# board1.net
KiCad netlist of a schematic drawn in EAGLE
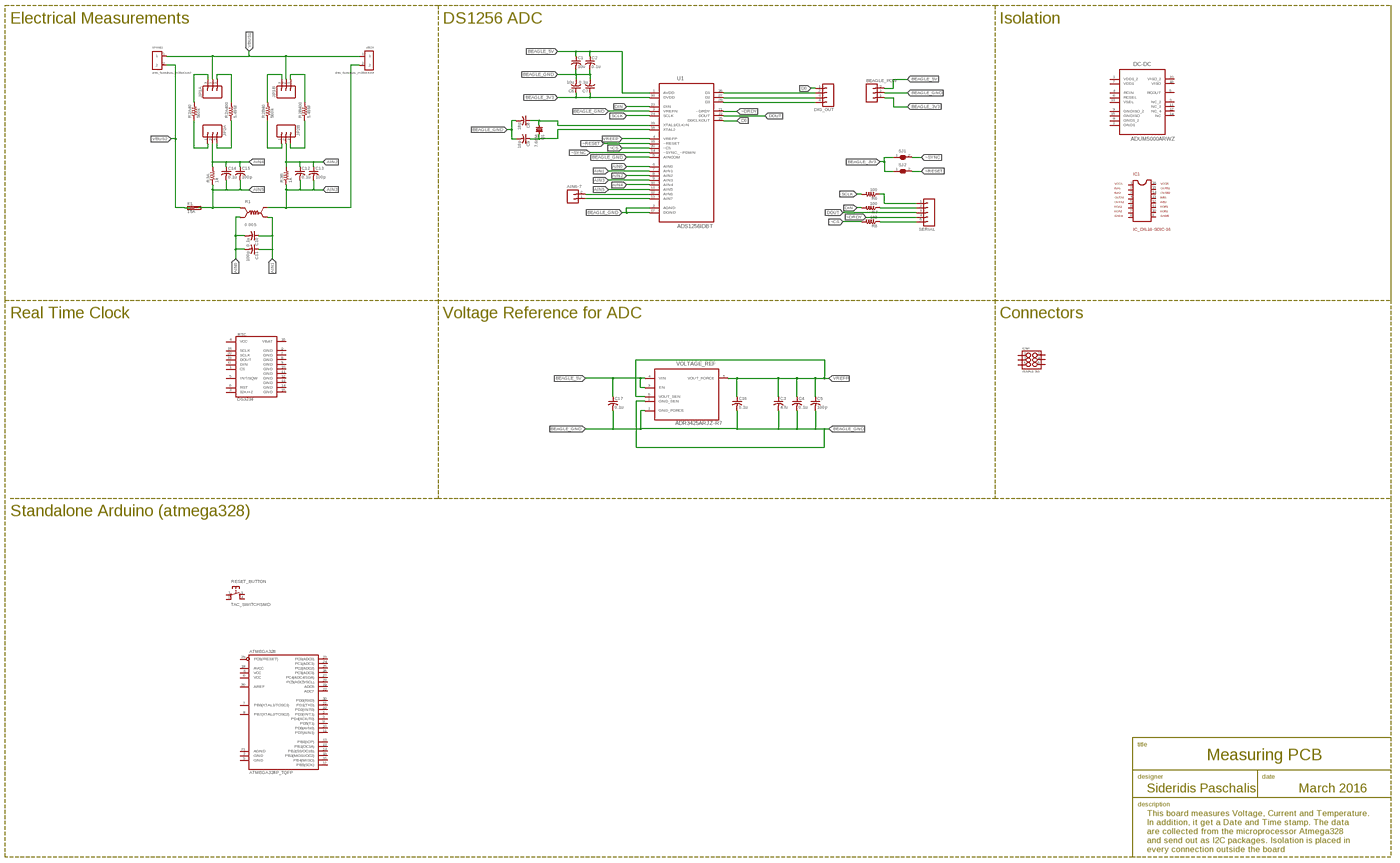
[diagram p0: schematic, sheet 1, overview]
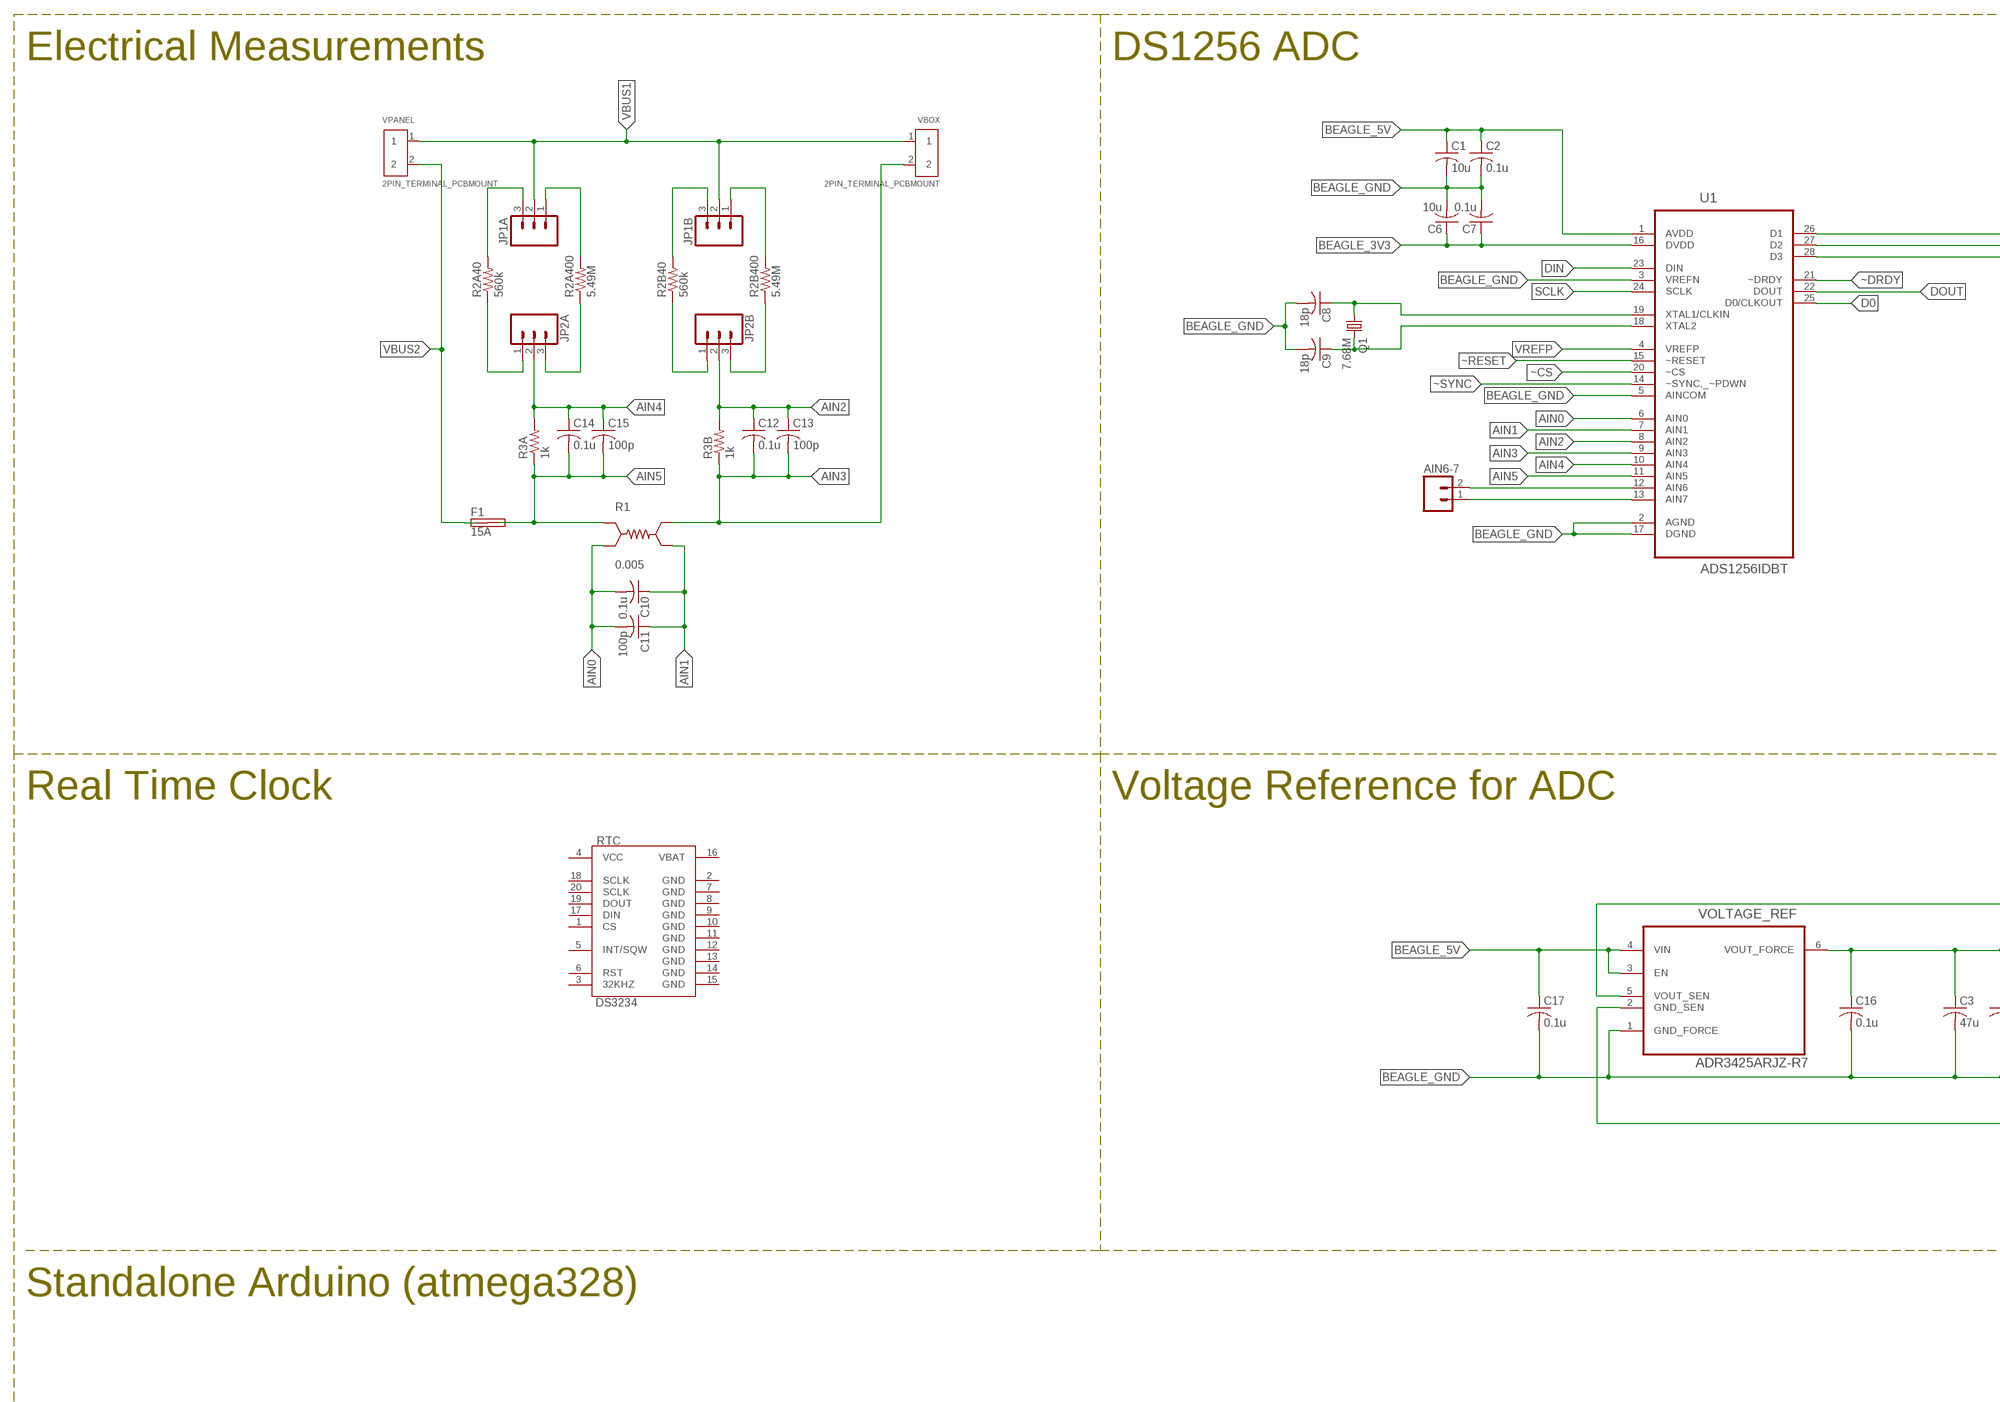
[diagram p1: schematic, sheet 1, part 1 of 4]
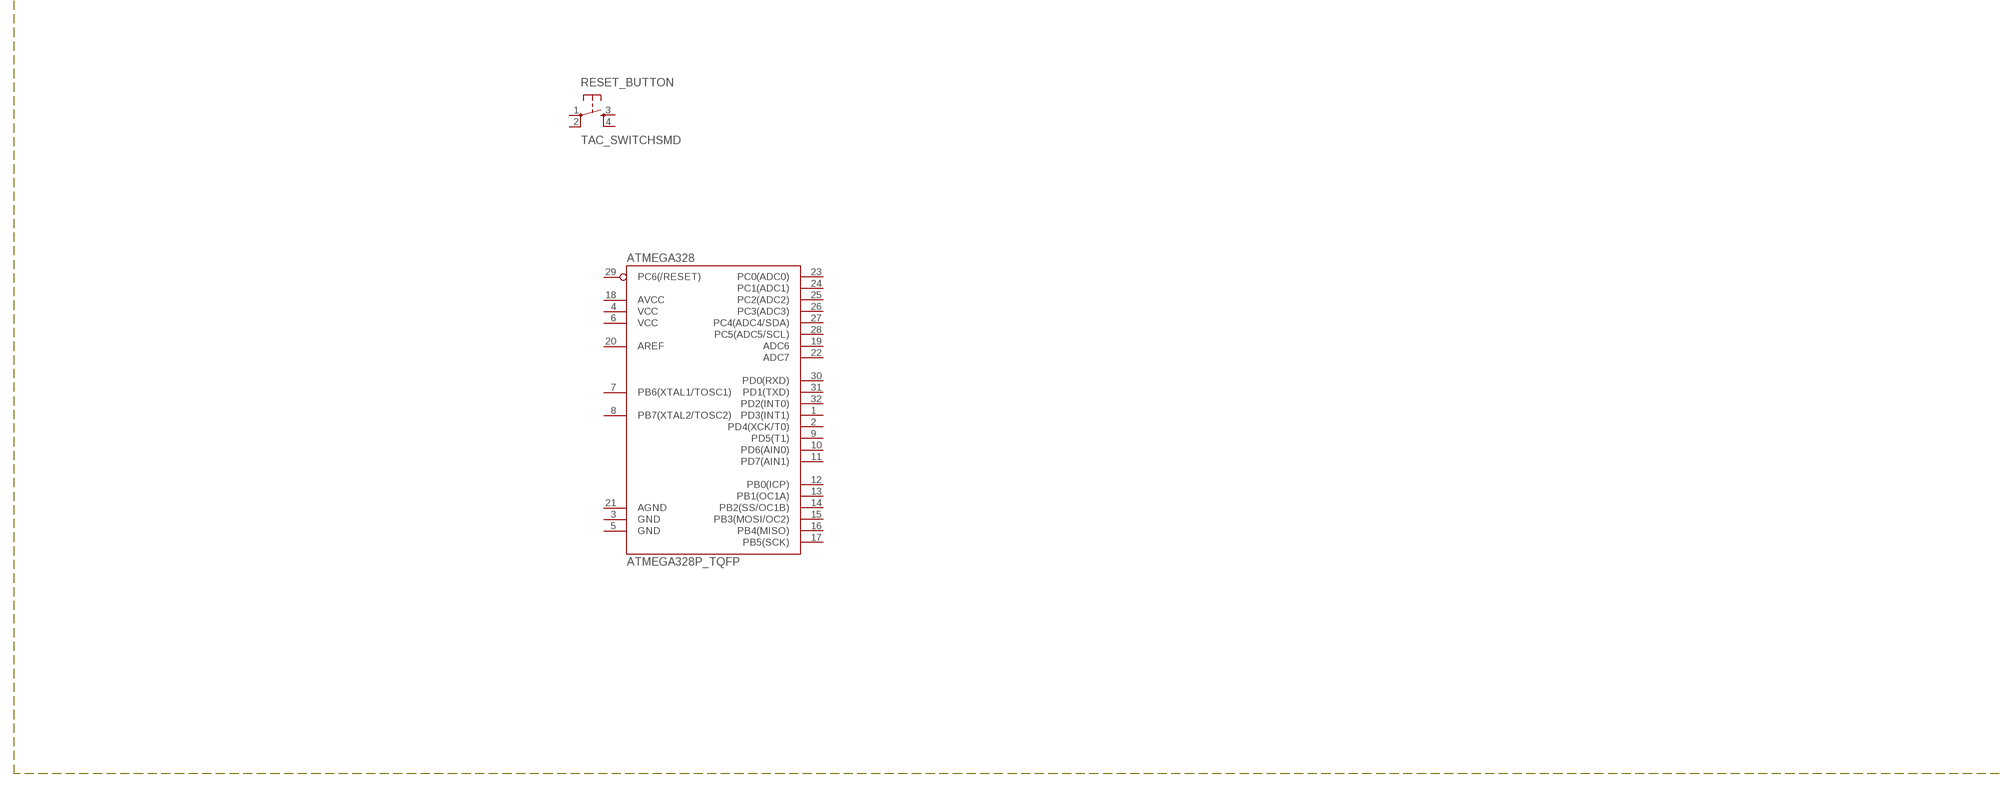
[diagram p2: schematic, sheet 1, part 2 of 4]
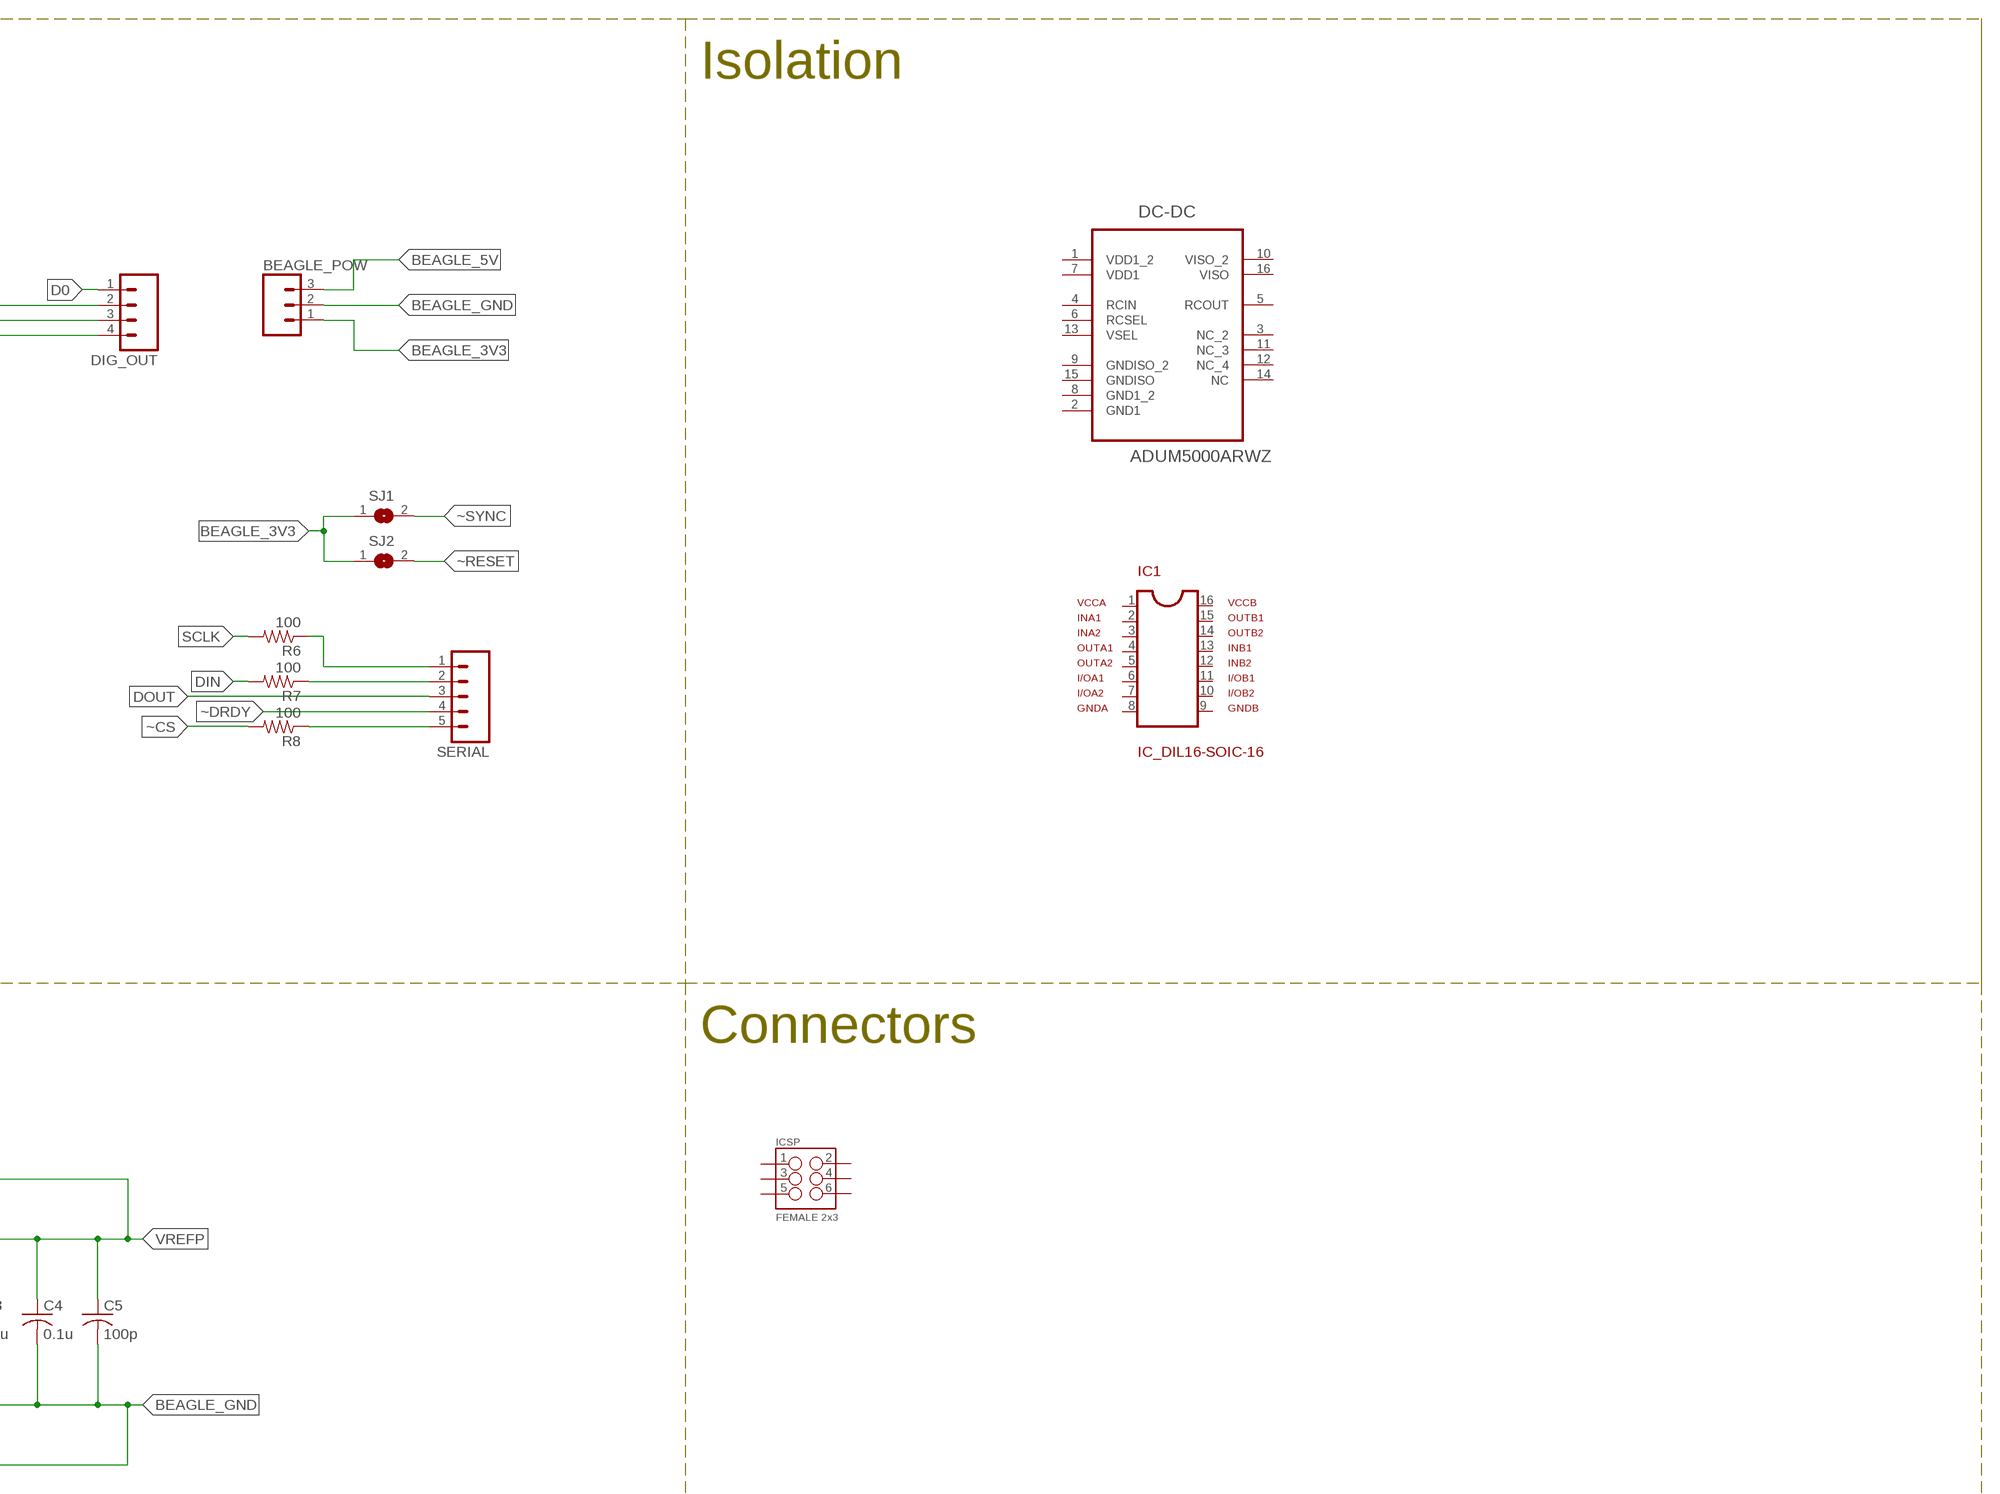
[diagram p3: schematic, sheet 1, part 3 of 4]
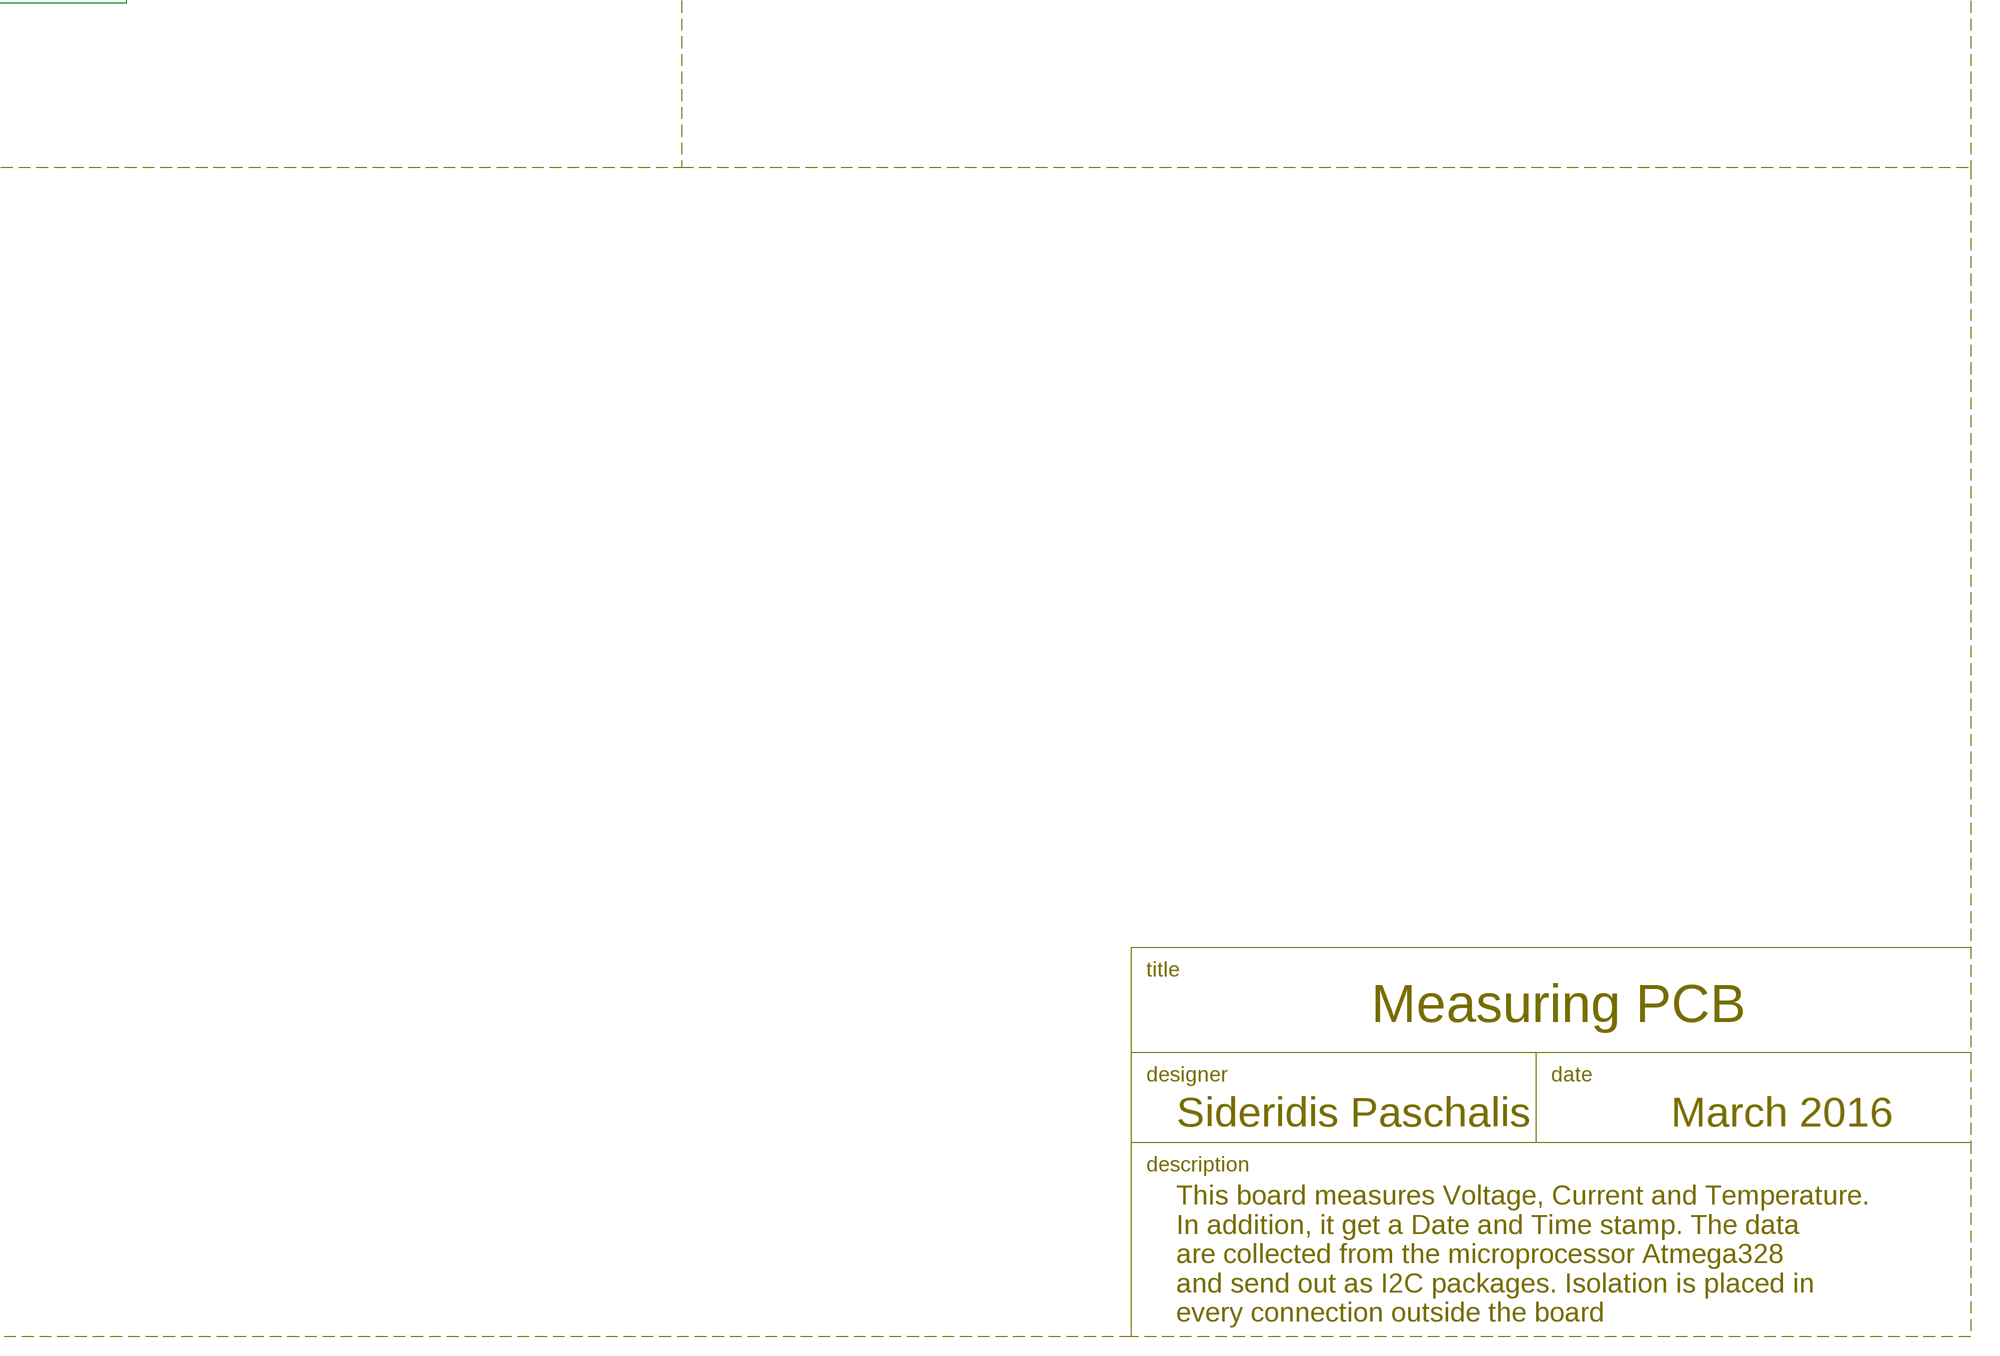
[diagram p4: schematic, sheet 1, part 4 of 4]

(export (version "E")
  (design (tool "Eeschema 10.0.6"))
  (components
    (comp (ref "AIN6-7")
      (value "M02PTH")
      (footprint "eagle-import:1X02")
      (libsource (lib "eagle-import") (part "M02PTH"))
    )
    (comp (ref "ATMEGA328")
      (value "ATMEGA328P_TQFP")
      (footprint "eagle-import:TQFP32-08")
      (libsource (lib "eagle-import") (part "ATMEGA328P_TQFP"))
    )
    (comp (ref "BEAGLE_POW")
      (value "M03PTH")
      (footprint "eagle-import:1X03")
      (libsource (lib "eagle-import") (part "M03PTH"))
    )
    (comp (ref "C1")
      (value "10u")
      (footprint "eagle-import:C3216")
      (libsource (lib "eagle-import") (part "C-USC3216"))
    )
    (comp (ref "C2")
      (value "0.1u")
      (footprint "eagle-import:C3216")
      (libsource (lib "eagle-import") (part "C-USC3216"))
    )
    (comp (ref "C3")
      (value "47u")
      (footprint "eagle-import:C3216")
      (libsource (lib "eagle-import") (part "C-USC3216"))
    )
    (comp (ref "C4")
      (value "0.1u")
      (footprint "eagle-import:C3216")
      (libsource (lib "eagle-import") (part "C-USC3216"))
    )
    (comp (ref "C5")
      (value "100p")
      (footprint "eagle-import:C3216")
      (libsource (lib "eagle-import") (part "C-USC3216"))
    )
    (comp (ref "C6")
      (value "10u")
      (footprint "eagle-import:C3216")
      (libsource (lib "eagle-import") (part "C-USC3216"))
    )
    (comp (ref "C7")
      (value "0.1u")
      (footprint "eagle-import:C3216")
      (libsource (lib "eagle-import") (part "C-USC3216"))
    )
    (comp (ref "C8")
      (value "18p")
      (footprint "eagle-import:C3216")
      (libsource (lib "eagle-import") (part "C-USC3216"))
    )
    (comp (ref "C9")
      (value "18p")
      (footprint "eagle-import:C3216")
      (libsource (lib "eagle-import") (part "C-USC3216"))
    )
    (comp (ref "C10")
      (value "0.1u")
      (footprint "eagle-import:C3216")
      (libsource (lib "eagle-import") (part "C-USC3216"))
    )
    (comp (ref "C11")
      (value "100p")
      (footprint "eagle-import:C3216")
      (libsource (lib "eagle-import") (part "C-USC3216"))
    )
    (comp (ref "C12")
      (value "0.1u")
      (footprint "eagle-import:C3216")
      (libsource (lib "eagle-import") (part "C-USC3216"))
    )
    (comp (ref "C13")
      (value "100p")
      (footprint "eagle-import:C3216")
      (libsource (lib "eagle-import") (part "C-USC3216"))
    )
    (comp (ref "C14")
      (value "0.1u")
      (footprint "eagle-import:C3216")
      (libsource (lib "eagle-import") (part "C-USC3216"))
    )
    (comp (ref "C15")
      (value "100p")
      (footprint "eagle-import:C3216")
      (libsource (lib "eagle-import") (part "C-USC3216"))
    )
    (comp (ref "C16")
      (value "0.1u")
      (footprint "eagle-import:C3216")
      (libsource (lib "eagle-import") (part "C-USC3216"))
    )
    (comp (ref "C17")
      (value "0.1u")
      (footprint "eagle-import:C3216")
      (libsource (lib "eagle-import") (part "C-USC3216"))
    )
    (comp (ref "DC-DC")
      (value "ADUM5000ARWZ")
      (footprint "eagle-import:SOIC127P1032X265-16N")
      (libsource (lib "eagle-import") (part "ADUM5000ARWZ"))
    )
    (comp (ref "DIG_OUT")
      (value "M04PTH")
      (footprint "eagle-import:1X04")
      (libsource (lib "eagle-import") (part "M04PTH"))
    )
    (comp (ref "F1")
      (value "15A")
      (footprint "eagle-import:SHK20L")
      (libsource (lib "eagle-import") (part "SHK20L"))
    )
    (comp (ref "IC1")
      (value "IC_DIL16-SOIC-16")
      (footprint "eagle-import:SOIC-16")
      (libsource (lib "eagle-import") (part "IC_DIL16-SOIC-16"))
    )
    (comp (ref "ICSP")
      (value "FEMALE 2x3")
      (footprint "eagle-import:2X3")
      (libsource (lib "eagle-import") (part "M03X2FEMALE"))
    )
    (comp (ref "JP1A")
      (value "M03PTH")
      (footprint "eagle-import:1X03")
      (libsource (lib "eagle-import") (part "M03PTH"))
    )
    (comp (ref "JP1B")
      (value "M03PTH")
      (footprint "eagle-import:1X03")
      (libsource (lib "eagle-import") (part "M03PTH"))
    )
    (comp (ref "JP2A")
      (value "M03PTH")
      (footprint "eagle-import:1X03")
      (libsource (lib "eagle-import") (part "M03PTH"))
    )
    (comp (ref "JP2B")
      (value "M03PTH")
      (footprint "eagle-import:1X03")
      (libsource (lib "eagle-import") (part "M03PTH"))
    )
    (comp (ref "Q1")
      (value "7.68M")
      (footprint "eagle-import:HC49U-V")
      (libsource (lib "eagle-import") (part "CRYSTALHC49U-V"))
    )
    (comp (ref "R1")
      (value "0.005")
      (footprint "eagle-import:LVK25")
      (libsource (lib "eagle-import") (part "LVK25R001"))
    )
    (comp (ref "R2A40")
      (value "560k")
      (footprint "eagle-import:M3216")
      (libsource (lib "eagle-import") (part "R-US_M3216"))
    )
    (comp (ref "R2A400")
      (value "5.49M")
      (footprint "eagle-import:M3216")
      (libsource (lib "eagle-import") (part "R-US_M3216"))
    )
    (comp (ref "R2B40")
      (value "560k")
      (footprint "eagle-import:M3216")
      (libsource (lib "eagle-import") (part "R-US_M3216"))
    )
    (comp (ref "R2B400")
      (value "5.49M")
      (footprint "eagle-import:M3216")
      (libsource (lib "eagle-import") (part "R-US_M3216"))
    )
    (comp (ref "R3A")
      (value "1k")
      (footprint "eagle-import:M3216")
      (libsource (lib "eagle-import") (part "R-US_M3216"))
    )
    (comp (ref "R3B")
      (value "1k")
      (footprint "eagle-import:M3216")
      (libsource (lib "eagle-import") (part "R-US_M3216"))
    )
    (comp (ref "R6")
      (value "100")
      (footprint "eagle-import:M3216")
      (libsource (lib "eagle-import") (part "R-US_M3216"))
    )
    (comp (ref "R7")
      (value "100")
      (footprint "eagle-import:M3216")
      (libsource (lib "eagle-import") (part "R-US_M3216"))
    )
    (comp (ref "R8")
      (value "100")
      (footprint "eagle-import:M3216")
      (libsource (lib "eagle-import") (part "R-US_M3216"))
    )
    (comp (ref "RESET_BUTTON")
      (value "TAC_SWITCHSMD")
      (footprint "eagle-import:TACTILE-SWITCH-SMD")
      (libsource (lib "eagle-import") (part "TAC_SWITCHSMD"))
    )
    (comp (ref "RTC")
      (value "DS3234")
      (footprint "eagle-import:DS3234")
      (libsource (lib "eagle-import") (part "DS3234"))
    )
    (comp (ref "SERIAL")
      (value "M05PTH")
      (footprint "eagle-import:1X05")
      (libsource (lib "eagle-import") (part "M05PTH"))
    )
    (comp (ref "SJ1") (value "SJ") (footprint "eagle-import:SJ") (libsource (lib "eagle-import") (part "SJ")))
    (comp (ref "SJ2") (value "SJ") (footprint "eagle-import:SJ") (libsource (lib "eagle-import") (part "SJ")))
    (comp (ref "U1")
      (value "ADS1256IDBT")
      (footprint "eagle-import:SOP65P780X200-28N")
      (libsource (lib "eagle-import") (part "ADS1256IDBT"))
    )
    (comp (ref "VBOX")
      (value "2PIN_TERMINAL_PCBMOUNT")
      (footprint "eagle-import:2TERMINALBLOCK_10MMPITCH")
      (libsource (lib "eagle-import") (part "2PIN_TERMINAL_PCBMOUNT"))
    )
    (comp (ref "VOLTAGE_REF")
      (value "ADR3425ARJZ-R7")
      (footprint "eagle-import:SOT95P280X145-6N")
      (libsource (lib "eagle-import") (part "ADR3425ARJZ-R7"))
    )
    (comp (ref "VPANEL")
      (value "2PIN_TERMINAL_PCBMOUNT")
      (footprint "eagle-import:2TERMINALBLOCK_10MMPITCH")
      (libsource (lib "eagle-import") (part "2PIN_TERMINAL_PCBMOUNT"))
    )
  )
  (nets
    (net (code "1") (name "/VDD1") (class "Default")
      (node (ref "DC-DC") (pin "7") (pinfunction "VDD1_7") (pintype "power_in"))
    )
    (net (code "2") (name "/VDD1_2") (class "Default")
      (node (ref "DC-DC") (pin "1") (pinfunction "VDD1_2_1") (pintype "power_in"))
    )
    (net (code "3") (name "/~{CS}") (class "Default")
      (node (ref "R8") (pin "2") (pinfunction "2_2") (pintype "passive"))
      (node (ref "U1") (pin "20") (pinfunction "~{CS}_20") (pintype "input"))
    )
    (net (code "4") (name "/~{DRDY}") (class "Default")
      (node (ref "SERIAL") (pin "4") (pinfunction "4_4") (pintype "passive"))
      (node (ref "U1") (pin "21") (pinfunction "~{DRDY}_21") (pintype "output"))
    )
    (net (code "5") (name "/~{RESET}") (class "Default")
      (node (ref "SJ2") (pin "2") (pinfunction "2_2") (pintype "passive"))
      (node (ref "U1") (pin "15") (pinfunction "~{RESET}_15") (pintype "input"))
    )
    (net (code "6") (name "/~{SYNC}") (class "Default")
      (node (ref "SJ1") (pin "2") (pinfunction "2_2") (pintype "passive"))
      (node (ref "U1") (pin "14") (pinfunction "~{SYNC,_}PDWN_14") (pintype "input"))
    )
    (net (code "7") (name "AIN0") (class "Default")
      (node (ref "C10") (pin "2") (pinfunction "2_2") (pintype "passive"))
      (node (ref "C11") (pin "2") (pinfunction "2_2") (pintype "passive"))
      (node (ref "R1") (pin "INV") (pinfunction "2_INV") (pintype "passive"))
      (node (ref "U1") (pin "6") (pinfunction "AIN0_6") (pintype "input"))
    )
    (net (code "8") (name "AIN1") (class "Default")
      (node (ref "C10") (pin "1") (pinfunction "1_1") (pintype "passive"))
      (node (ref "C11") (pin "1") (pinfunction "1_1") (pintype "passive"))
      (node (ref "R1") (pin "OUTV") (pinfunction "4_OUTV") (pintype "passive"))
      (node (ref "U1") (pin "7") (pinfunction "AIN1_7") (pintype "input"))
    )
    (net (code "9") (name "AIN2") (class "Default")
      (node (ref "C12") (pin "1") (pinfunction "1_1") (pintype "passive"))
      (node (ref "C13") (pin "1") (pinfunction "1_1") (pintype "passive"))
      (node (ref "JP2B") (pin "2") (pinfunction "2_2") (pintype "passive"))
      (node (ref "R3B") (pin "2") (pinfunction "2_2") (pintype "passive"))
      (node (ref "U1") (pin "8") (pinfunction "AIN2_8") (pintype "input"))
    )
    (net (code "10") (name "AIN3") (class "Default")
      (node (ref "C12") (pin "2") (pinfunction "2_2") (pintype "passive"))
      (node (ref "C13") (pin "2") (pinfunction "2_2") (pintype "passive"))
      (node (ref "R1") (pin "OUTI") (pinfunction "3_OUTI") (pintype "passive"))
      (node (ref "R3B") (pin "1") (pinfunction "1_1") (pintype "passive"))
      (node (ref "U1") (pin "9") (pinfunction "AIN3_9") (pintype "input"))
      (node (ref "VBOX") (pin "2") (pinfunction "2_2") (pintype "bidirectional"))
    )
    (net (code "11") (name "AIN4") (class "Default")
      (node (ref "C14") (pin "1") (pinfunction "1_1") (pintype "passive"))
      (node (ref "C15") (pin "1") (pinfunction "1_1") (pintype "passive"))
      (node (ref "JP2A") (pin "2") (pinfunction "2_2") (pintype "passive"))
      (node (ref "R3A") (pin "2") (pinfunction "2_2") (pintype "passive"))
      (node (ref "U1") (pin "10") (pinfunction "AIN4_10") (pintype "input"))
    )
    (net (code "12") (name "AIN5") (class "Default")
      (node (ref "C14") (pin "2") (pinfunction "2_2") (pintype "passive"))
      (node (ref "C15") (pin "2") (pinfunction "2_2") (pintype "passive"))
      (node (ref "F1") (pin "2A") (pinfunction "2A_2A") (pintype "passive"))
      (node (ref "F1") (pin "2B") (pinfunction "2B_2B") (pintype "passive"))
      (node (ref "R1") (pin "INI") (pinfunction "1_INI") (pintype "passive"))
      (node (ref "R3A") (pin "1") (pinfunction "1_1") (pintype "passive"))
      (node (ref "U1") (pin "11") (pinfunction "AIN5_11") (pintype "input"))
    )
    (net (code "13") (name "BEAGLE_3V3") (class "Default")
      (node (ref "BEAGLE_POW") (pin "1") (pinfunction "1_1") (pintype "passive"))
      (node (ref "C6") (pin "1") (pinfunction "1_1") (pintype "passive"))
      (node (ref "C7") (pin "1") (pinfunction "1_1") (pintype "passive"))
      (node (ref "SJ1") (pin "1") (pinfunction "1_1") (pintype "passive"))
      (node (ref "SJ2") (pin "1") (pinfunction "1_1") (pintype "passive"))
      (node (ref "U1") (pin "16") (pinfunction "DVDD_16") (pintype "power_in"))
    )
    (net (code "14") (name "BEAGLE_5V") (class "Default")
      (node (ref "BEAGLE_POW") (pin "3") (pinfunction "3_3") (pintype "passive"))
      (node (ref "C1") (pin "1") (pinfunction "1_1") (pintype "passive"))
      (node (ref "C17") (pin "1") (pinfunction "1_1") (pintype "passive"))
      (node (ref "C2") (pin "1") (pinfunction "1_1") (pintype "passive"))
      (node (ref "U1") (pin "1") (pinfunction "AVDD_1") (pintype "power_in"))
      (node (ref "VOLTAGE_REF") (pin "3") (pinfunction "EN_3") (pintype "input"))
      (node (ref "VOLTAGE_REF") (pin "4") (pinfunction "VIN_4") (pintype "power_in"))
    )
    (net (code "15") (name "BEAGLE_GND") (class "Default")
      (node (ref "BEAGLE_POW") (pin "2") (pinfunction "2_2") (pintype "passive"))
      (node (ref "C1") (pin "2") (pinfunction "2_2") (pintype "passive"))
      (node (ref "C16") (pin "2") (pinfunction "2_2") (pintype "passive"))
      (node (ref "C17") (pin "2") (pinfunction "2_2") (pintype "passive"))
      (node (ref "C2") (pin "2") (pinfunction "2_2") (pintype "passive"))
      (node (ref "C3") (pin "2") (pinfunction "2_2") (pintype "passive"))
      (node (ref "C4") (pin "2") (pinfunction "2_2") (pintype "passive"))
      (node (ref "C5") (pin "2") (pinfunction "2_2") (pintype "passive"))
      (node (ref "C6") (pin "2") (pinfunction "2_2") (pintype "passive"))
      (node (ref "C7") (pin "2") (pinfunction "2_2") (pintype "passive"))
      (node (ref "C8") (pin "2") (pinfunction "2_2") (pintype "passive"))
      (node (ref "C9") (pin "2") (pinfunction "2_2") (pintype "passive"))
      (node (ref "U1") (pin "17") (pinfunction "DGND_17") (pintype "passive"))
      (node (ref "U1") (pin "2") (pinfunction "AGND_2") (pintype "passive"))
      (node (ref "U1") (pin "3") (pinfunction "VREFN_3") (pintype "input"))
      (node (ref "U1") (pin "5") (pinfunction "AINCOM_5") (pintype "input"))
      (node (ref "VOLTAGE_REF") (pin "1") (pinfunction "GND_FORCE_1") (pintype "passive"))
      (node (ref "VOLTAGE_REF") (pin "2") (pinfunction "GND_SEN_2") (pintype "input"))
    )
    (net (code "16") (name "D0") (class "Default")
      (node (ref "DIG_OUT") (pin "1") (pinfunction "1_1") (pintype "passive"))
      (node (ref "U1") (pin "25") (pinfunction "D0/CLKOUT_25") (pintype "bidirectional"))
    )
    (net (code "17") (name "DIN") (class "Default")
      (node (ref "R7") (pin "2") (pinfunction "2_2") (pintype "passive"))
      (node (ref "U1") (pin "23") (pinfunction "DIN_23") (pintype "input"))
    )
    (net (code "18") (name "DOUT") (class "Default")
      (node (ref "SERIAL") (pin "3") (pinfunction "3_3") (pintype "passive"))
      (node (ref "U1") (pin "22") (pinfunction "DOUT_22") (pintype "output"))
    )
    (net (code "19") (name "Net-(JP1A-Pad1)") (class "Default")
      (node (ref "JP1A") (pin "1") (pinfunction "1_1") (pintype "passive"))
      (node (ref "R2A400") (pin "2") (pinfunction "2_2") (pintype "passive"))
    )
    (net (code "20") (name "Net-(JP1A-Pad3)") (class "Default")
      (node (ref "JP1A") (pin "3") (pinfunction "3_3") (pintype "passive"))
      (node (ref "R2A40") (pin "2") (pinfunction "2_2") (pintype "passive"))
    )
    (net (code "21") (name "Net-(JP1B-Pad1)") (class "Default")
      (node (ref "JP1B") (pin "1") (pinfunction "1_1") (pintype "passive"))
      (node (ref "R2B400") (pin "2") (pinfunction "2_2") (pintype "passive"))
    )
    (net (code "22") (name "Net-(JP1B-Pad3)") (class "Default")
      (node (ref "JP1B") (pin "3") (pinfunction "3_3") (pintype "passive"))
      (node (ref "R2B40") (pin "2") (pinfunction "2_2") (pintype "passive"))
    )
    (net (code "23") (name "Net-(JP2A-Pad1)") (class "Default")
      (node (ref "JP2A") (pin "1") (pinfunction "1_1") (pintype "passive"))
      (node (ref "R2A40") (pin "1") (pinfunction "1_1") (pintype "passive"))
    )
    (net (code "24") (name "Net-(JP2A-Pad3)") (class "Default")
      (node (ref "JP2A") (pin "3") (pinfunction "3_3") (pintype "passive"))
      (node (ref "R2A400") (pin "1") (pinfunction "1_1") (pintype "passive"))
    )
    (net (code "25") (name "Net-(JP2B-Pad1)") (class "Default")
      (node (ref "JP2B") (pin "1") (pinfunction "1_1") (pintype "passive"))
      (node (ref "R2B40") (pin "1") (pinfunction "1_1") (pintype "passive"))
    )
    (net (code "26") (name "Net-(JP2B-Pad3)") (class "Default")
      (node (ref "JP2B") (pin "3") (pinfunction "3_3") (pintype "passive"))
      (node (ref "R2B400") (pin "1") (pinfunction "1_1") (pintype "passive"))
    )
    (net (code "27") (name "Net-(R6-Pad1)") (class "Default")
      (node (ref "R6") (pin "1") (pinfunction "1_1") (pintype "passive"))
      (node (ref "SERIAL") (pin "1") (pinfunction "1_1") (pintype "passive"))
    )
    (net (code "28") (name "Net-(R7-Pad1)") (class "Default")
      (node (ref "R7") (pin "1") (pinfunction "1_1") (pintype "passive"))
      (node (ref "SERIAL") (pin "2") (pinfunction "2_2") (pintype "passive"))
    )
    (net (code "29") (name "Net-(R8-Pad1)") (class "Default")
      (node (ref "R8") (pin "1") (pinfunction "1_1") (pintype "passive"))
      (node (ref "SERIAL") (pin "5") (pinfunction "5_5") (pintype "passive"))
    )
    (net (code "30") (name "Net-(U1-AIN6)") (class "Default")
      (node (ref "AIN6-7") (pin "2") (pinfunction "2_2") (pintype "passive"))
      (node (ref "U1") (pin "12") (pinfunction "AIN6_12") (pintype "input"))
    )
    (net (code "31") (name "Net-(U1-AIN7)") (class "Default")
      (node (ref "AIN6-7") (pin "1") (pinfunction "1_1") (pintype "passive"))
      (node (ref "U1") (pin "13") (pinfunction "AIN7_13") (pintype "input"))
    )
    (net (code "32") (name "Net-(U1-D1)") (class "Default")
      (node (ref "DIG_OUT") (pin "2") (pinfunction "2_2") (pintype "passive"))
      (node (ref "U1") (pin "26") (pinfunction "D1_26") (pintype "bidirectional"))
    )
    (net (code "33") (name "Net-(U1-D2)") (class "Default")
      (node (ref "DIG_OUT") (pin "3") (pinfunction "3_3") (pintype "passive"))
      (node (ref "U1") (pin "27") (pinfunction "D2_27") (pintype "bidirectional"))
    )
    (net (code "34") (name "Net-(U1-D3)") (class "Default")
      (node (ref "DIG_OUT") (pin "4") (pinfunction "4_4") (pintype "passive"))
      (node (ref "U1") (pin "28") (pinfunction "D3_28") (pintype "bidirectional"))
    )
    (net (code "35") (name "Net-(U1-XTAL1{slash}CLKIN)") (class "Default")
      (node (ref "C8") (pin "1") (pinfunction "1_1") (pintype "passive"))
      (node (ref "Q1") (pin "1") (pinfunction "1_1") (pintype "passive"))
      (node (ref "U1") (pin "19") (pinfunction "XTAL1/CLKIN_19") (pintype "input"))
    )
    (net (code "36") (name "Net-(U1-XTAL2)") (class "Default")
      (node (ref "C9") (pin "1") (pinfunction "1_1") (pintype "passive"))
      (node (ref "Q1") (pin "2") (pinfunction "2_2") (pintype "passive"))
      (node (ref "U1") (pin "18") (pinfunction "XTAL2_18") (pintype "input"))
    )
    (net (code "37") (name "SCLK") (class "Default")
      (node (ref "R6") (pin "2") (pinfunction "2_2") (pintype "passive"))
      (node (ref "U1") (pin "24") (pinfunction "SCLK_24") (pintype "input"))
    )
    (net (code "38") (name "VBUS1") (class "Default")
      (node (ref "JP1A") (pin "2") (pinfunction "2_2") (pintype "passive"))
      (node (ref "JP1B") (pin "2") (pinfunction "2_2") (pintype "passive"))
      (node (ref "VBOX") (pin "1") (pinfunction "1_1") (pintype "bidirectional"))
      (node (ref "VPANEL") (pin "1") (pinfunction "1_1") (pintype "bidirectional"))
    )
    (net (code "39") (name "VBUS2") (class "Default")
      (node (ref "F1") (pin "1A") (pinfunction "1A_1A") (pintype "passive"))
      (node (ref "F1") (pin "1B") (pinfunction "1B_1B") (pintype "passive"))
      (node (ref "VPANEL") (pin "2") (pinfunction "2_2") (pintype "bidirectional"))
    )
    (net (code "40") (name "VREFP") (class "Default")
      (node (ref "C16") (pin "1") (pinfunction "1_1") (pintype "passive"))
      (node (ref "C3") (pin "1") (pinfunction "1_1") (pintype "passive"))
      (node (ref "C4") (pin "1") (pinfunction "1_1") (pintype "passive"))
      (node (ref "C5") (pin "1") (pinfunction "1_1") (pintype "passive"))
      (node (ref "U1") (pin "4") (pinfunction "VREFP_4") (pintype "input"))
      (node (ref "VOLTAGE_REF") (pin "5") (pinfunction "VOUT_SEN_5") (pintype "input"))
      (node (ref "VOLTAGE_REF") (pin "6") (pinfunction "VOUT_FORCE_6") (pintype "output"))
    )
    (net (code "41") (name "unconnected-(ATMEGA328-ADC6-Pad19)") (class "Default")
      (node (ref "ATMEGA328") (pin "19") (pinfunction "ADC6_19") (pintype "bidirectional"))
    )
    (net (code "42") (name "unconnected-(ATMEGA328-ADC7-Pad22)") (class "Default")
      (node (ref "ATMEGA328") (pin "22") (pinfunction "ADC7_22") (pintype "bidirectional"))
    )
    (net (code "43") (name "unconnected-(ATMEGA328-AGND-Pad21)") (class "Default")
      (node (ref "ATMEGA328") (pin "21") (pinfunction "AGND_21") (pintype "bidirectional"))
    )
    (net (code "44") (name "unconnected-(ATMEGA328-AREF-Pad20)") (class "Default")
      (node (ref "ATMEGA328") (pin "20") (pinfunction "AREF_20") (pintype "bidirectional"))
    )
    (net (code "45") (name "unconnected-(ATMEGA328-AVCC-Pad18)") (class "Default")
      (node (ref "ATMEGA328") (pin "18") (pinfunction "AVCC_18") (pintype "bidirectional"))
    )
    (net (code "46") (name "unconnected-(ATMEGA328-GND-Pad3)") (class "Default")
      (node (ref "ATMEGA328") (pin "3") (pinfunction "GND_3") (pintype "bidirectional"))
    )
    (net (code "47") (name "unconnected-(ATMEGA328-GND-Pad5)") (class "Default")
      (node (ref "ATMEGA328") (pin "5") (pinfunction "GND_5") (pintype "bidirectional"))
    )
    (net (code "48") (name "unconnected-(ATMEGA328-PB0(ICP)-Pad12)") (class "Default")
      (node (ref "ATMEGA328") (pin "12") (pinfunction "PB0(ICP)_12") (pintype "bidirectional"))
    )
    (net (code "49") (name "unconnected-(ATMEGA328-PB1(OC1A)-Pad13)") (class "Default")
      (node (ref "ATMEGA328") (pin "13") (pinfunction "PB1(OC1A)_13") (pintype "bidirectional"))
    )
    (net (code "50") (name "unconnected-(ATMEGA328-PB2(SS{slash}OC1B)-Pad14)") (class "Default")
      (node (ref "ATMEGA328") (pin "14") (pinfunction "PB2(SS/OC1B)_14") (pintype "bidirectional"))
    )
    (net (code "51") (name "unconnected-(ATMEGA328-PB3(MOSI{slash}OC2)-Pad15)") (class "Default")
      (node (ref "ATMEGA328") (pin "15") (pinfunction "PB3(MOSI/OC2)_15") (pintype "bidirectional"))
    )
    (net (code "52") (name "unconnected-(ATMEGA328-PB4(MISO)-Pad16)") (class "Default")
      (node (ref "ATMEGA328") (pin "16") (pinfunction "PB4(MISO)_16") (pintype "bidirectional"))
    )
    (net (code "53") (name "unconnected-(ATMEGA328-PB5(SCK)-Pad17)") (class "Default")
      (node (ref "ATMEGA328") (pin "17") (pinfunction "PB5(SCK)_17") (pintype "bidirectional"))
    )
    (net (code "54") (name "unconnected-(ATMEGA328-PB6(XTAL1{slash}TOSC1)-Pad7)") (class "Default")
      (node (ref "ATMEGA328") (pin "7") (pinfunction "PB6(XTAL1/TOSC1)_7") (pintype "bidirectional"))
    )
    (net (code "55") (name "unconnected-(ATMEGA328-PB7(XTAL2{slash}TOSC2)-Pad8)") (class "Default")
      (node (ref "ATMEGA328") (pin "8") (pinfunction "PB7(XTAL2/TOSC2)_8") (pintype "bidirectional"))
    )
    (net (code "56") (name "unconnected-(ATMEGA328-PC0(ADC0)-Pad23)") (class "Default")
      (node (ref "ATMEGA328") (pin "23") (pinfunction "PC0(ADC0)_23") (pintype "bidirectional"))
    )
    (net (code "57") (name "unconnected-(ATMEGA328-PC1(ADC1)-Pad24)") (class "Default")
      (node (ref "ATMEGA328") (pin "24") (pinfunction "PC1(ADC1)_24") (pintype "bidirectional"))
    )
    (net (code "58") (name "unconnected-(ATMEGA328-PC2(ADC2)-Pad25)") (class "Default")
      (node (ref "ATMEGA328") (pin "25") (pinfunction "PC2(ADC2)_25") (pintype "bidirectional"))
    )
    (net (code "59") (name "unconnected-(ATMEGA328-PC3(ADC3)-Pad26)") (class "Default")
      (node (ref "ATMEGA328") (pin "26") (pinfunction "PC3(ADC3)_26") (pintype "bidirectional"))
    )
    (net (code "60") (name "unconnected-(ATMEGA328-PC4(ADC4{slash}SDA)-Pad27)") (class "Default")
      (node (ref "ATMEGA328") (pin "27") (pinfunction "PC4(ADC4/SDA)_27") (pintype "bidirectional"))
    )
    (net (code "61") (name "unconnected-(ATMEGA328-PC5(ADC5{slash}SCL)-Pad28)") (class "Default")
      (node (ref "ATMEGA328") (pin "28") (pinfunction "PC5(ADC5/SCL)_28") (pintype "bidirectional"))
    )
    (net (code "62") (name "unconnected-(ATMEGA328-PC6({slash}RESET)-Pad29)") (class "Default")
      (node (ref "ATMEGA328") (pin "29") (pinfunction "PC6(/RESET)_29") (pintype "bidirectional"))
    )
    (net (code "63") (name "unconnected-(ATMEGA328-PD0(RXD)-Pad30)") (class "Default")
      (node (ref "ATMEGA328") (pin "30") (pinfunction "PD0(RXD)_30") (pintype "bidirectional"))
    )
    (net (code "64") (name "unconnected-(ATMEGA328-PD1(TXD)-Pad31)") (class "Default")
      (node (ref "ATMEGA328") (pin "31") (pinfunction "PD1(TXD)_31") (pintype "bidirectional"))
    )
    (net (code "65") (name "unconnected-(ATMEGA328-PD2(INT0)-Pad32)") (class "Default")
      (node (ref "ATMEGA328") (pin "32") (pinfunction "PD2(INT0)_32") (pintype "bidirectional"))
    )
    (net (code "66") (name "unconnected-(ATMEGA328-PD3(INT1)-Pad1)") (class "Default")
      (node (ref "ATMEGA328") (pin "1") (pinfunction "PD3(INT1)_1") (pintype "bidirectional"))
    )
    (net (code "67") (name "unconnected-(ATMEGA328-PD4(XCK{slash}T0)-Pad2)") (class "Default")
      (node (ref "ATMEGA328") (pin "2") (pinfunction "PD4(XCK/T0)_2") (pintype "bidirectional"))
    )
    (net (code "68") (name "unconnected-(ATMEGA328-PD5(T1)-Pad9)") (class "Default")
      (node (ref "ATMEGA328") (pin "9") (pinfunction "PD5(T1)_9") (pintype "bidirectional"))
    )
    (net (code "69") (name "unconnected-(ATMEGA328-PD6(AIN0)-Pad10)") (class "Default")
      (node (ref "ATMEGA328") (pin "10") (pinfunction "PD6(AIN0)_10") (pintype "bidirectional"))
    )
    (net (code "70") (name "unconnected-(ATMEGA328-PD7(AIN1)-Pad11)") (class "Default")
      (node (ref "ATMEGA328") (pin "11") (pinfunction "PD7(AIN1)_11") (pintype "bidirectional"))
    )
    (net (code "71") (name "unconnected-(ATMEGA328-VCC-Pad4)") (class "Default")
      (node (ref "ATMEGA328") (pin "4") (pinfunction "VCC_4") (pintype "bidirectional"))
    )
    (net (code "72") (name "unconnected-(ATMEGA328-VCC-Pad6)") (class "Default")
      (node (ref "ATMEGA328") (pin "6") (pinfunction "VCC_6") (pintype "bidirectional"))
    )
    (net (code "73") (name "unconnected-(DC-DC-GND1-Pad2)") (class "Default")
      (node (ref "DC-DC") (pin "2") (pinfunction "GND1_2") (pintype "passive"))
    )
    (net (code "74") (name "unconnected-(DC-DC-GND1_2-Pad8)") (class "Default")
      (node (ref "DC-DC") (pin "8") (pinfunction "GND1_2_8") (pintype "passive"))
    )
    (net (code "75") (name "unconnected-(DC-DC-GNDISO-Pad15)") (class "Default")
      (node (ref "DC-DC") (pin "15") (pinfunction "GNDISO_15") (pintype "passive"))
    )
    (net (code "76") (name "unconnected-(DC-DC-GNDISO_2-Pad9)") (class "Default")
      (node (ref "DC-DC") (pin "9") (pinfunction "GNDISO_2_9") (pintype "passive"))
    )
    (net (code "77") (name "unconnected-(DC-DC-NC-Pad14)") (class "Default")
      (node (ref "DC-DC") (pin "14") (pinfunction "NC_14") (pintype "no_connect"))
    )
    (net (code "78") (name "unconnected-(DC-DC-NC_2-Pad3)") (class "Default")
      (node (ref "DC-DC") (pin "3") (pinfunction "NC_2_3") (pintype "no_connect"))
    )
    (net (code "79") (name "unconnected-(DC-DC-NC_3-Pad11)") (class "Default")
      (node (ref "DC-DC") (pin "11") (pinfunction "NC_3_11") (pintype "no_connect"))
    )
    (net (code "80") (name "unconnected-(DC-DC-NC_4-Pad12)") (class "Default")
      (node (ref "DC-DC") (pin "12") (pinfunction "NC_4_12") (pintype "no_connect"))
    )
    (net (code "81") (name "unconnected-(DC-DC-RCIN-Pad4)") (class "Default")
      (node (ref "DC-DC") (pin "4") (pinfunction "RCIN_4") (pintype "input"))
    )
    (net (code "82") (name "unconnected-(DC-DC-RCOUT-Pad5)") (class "Default")
      (node (ref "DC-DC") (pin "5") (pinfunction "RCOUT_5") (pintype "output"))
    )
    (net (code "83") (name "unconnected-(DC-DC-RCSEL-Pad6)") (class "Default")
      (node (ref "DC-DC") (pin "6") (pinfunction "RCSEL_6") (pintype "input"))
    )
    (net (code "84") (name "unconnected-(DC-DC-VISO-Pad16)") (class "Default")
      (node (ref "DC-DC") (pin "16") (pinfunction "VISO_16") (pintype "output"))
    )
    (net (code "85") (name "unconnected-(DC-DC-VISO_2-Pad10)") (class "Default")
      (node (ref "DC-DC") (pin "10") (pinfunction "VISO_2_10") (pintype "output"))
    )
    (net (code "86") (name "unconnected-(DC-DC-VSEL-Pad13)") (class "Default")
      (node (ref "DC-DC") (pin "13") (pinfunction "VSEL_13") (pintype "input"))
    )
    (net (code "87") (name "unconnected-(IC1-GNDA-Pad8)") (class "Default")
      (node (ref "IC1") (pin "8") (pinfunction "GNDA_8") (pintype "bidirectional"))
    )
    (net (code "88") (name "unconnected-(IC1-GNDB-Pad9)") (class "Default")
      (node (ref "IC1") (pin "9") (pinfunction "GNDB_9") (pintype "bidirectional"))
    )
    (net (code "89") (name "unconnected-(IC1-INA1-Pad2)") (class "Default")
      (node (ref "IC1") (pin "2") (pinfunction "INA1_2") (pintype "bidirectional"))
    )
    (net (code "90") (name "unconnected-(IC1-INA2-Pad3)") (class "Default")
      (node (ref "IC1") (pin "3") (pinfunction "INA2_3") (pintype "bidirectional"))
    )
    (net (code "91") (name "unconnected-(IC1-INB1-Pad13)") (class "Default")
      (node (ref "IC1") (pin "13") (pinfunction "INB1_13") (pintype "bidirectional"))
    )
    (net (code "92") (name "unconnected-(IC1-INB2-Pad12)") (class "Default")
      (node (ref "IC1") (pin "12") (pinfunction "INB2_12") (pintype "bidirectional"))
    )
    (net (code "93") (name "unconnected-(IC1-I{slash}OA1-Pad6)") (class "Default")
      (node (ref "IC1") (pin "6") (pinfunction "I/OA1_6") (pintype "bidirectional"))
    )
    (net (code "94") (name "unconnected-(IC1-I{slash}OA2-Pad7)") (class "Default")
      (node (ref "IC1") (pin "7") (pinfunction "I/OA2_7") (pintype "bidirectional"))
    )
    (net (code "95") (name "unconnected-(IC1-I{slash}OB1-Pad11)") (class "Default")
      (node (ref "IC1") (pin "11") (pinfunction "I/OB1_11") (pintype "bidirectional"))
    )
    (net (code "96") (name "unconnected-(IC1-I{slash}OB2-Pad10)") (class "Default")
      (node (ref "IC1") (pin "10") (pinfunction "I/OB2_10") (pintype "bidirectional"))
    )
    (net (code "97") (name "unconnected-(IC1-OUTA1-Pad4)") (class "Default")
      (node (ref "IC1") (pin "4") (pinfunction "OUTA1_4") (pintype "bidirectional"))
    )
    (net (code "98") (name "unconnected-(IC1-OUTA2-Pad5)") (class "Default")
      (node (ref "IC1") (pin "5") (pinfunction "OUTA2_5") (pintype "bidirectional"))
    )
    (net (code "99") (name "unconnected-(IC1-OUTB1-Pad15)") (class "Default")
      (node (ref "IC1") (pin "15") (pinfunction "OUTB1_15") (pintype "bidirectional"))
    )
    (net (code "100") (name "unconnected-(IC1-OUTB2-Pad14)") (class "Default")
      (node (ref "IC1") (pin "14") (pinfunction "OUTB2_14") (pintype "bidirectional"))
    )
    (net (code "101") (name "unconnected-(IC1-VCCA-Pad1)") (class "Default")
      (node (ref "IC1") (pin "1") (pinfunction "VCCA_1") (pintype "bidirectional"))
    )
    (net (code "102") (name "unconnected-(IC1-VCCB-Pad16)") (class "Default")
      (node (ref "IC1") (pin "16") (pinfunction "VCCB_16") (pintype "bidirectional"))
    )
    (net (code "103") (name "unconnected-(ICSP-Pad1)") (class "Default")
      (node (ref "ICSP") (pin "1") (pinfunction "1_1") (pintype "bidirectional"))
    )
    (net (code "104") (name "unconnected-(ICSP-Pad2)") (class "Default")
      (node (ref "ICSP") (pin "2") (pinfunction "2_2") (pintype "bidirectional"))
    )
    (net (code "105") (name "unconnected-(ICSP-Pad3)") (class "Default")
      (node (ref "ICSP") (pin "3") (pinfunction "3_3") (pintype "bidirectional"))
    )
    (net (code "106") (name "unconnected-(ICSP-Pad4)") (class "Default")
      (node (ref "ICSP") (pin "4") (pinfunction "4_4") (pintype "bidirectional"))
    )
    (net (code "107") (name "unconnected-(ICSP-Pad5)") (class "Default")
      (node (ref "ICSP") (pin "5") (pinfunction "5_5") (pintype "bidirectional"))
    )
    (net (code "108") (name "unconnected-(ICSP-Pad6)") (class "Default")
      (node (ref "ICSP") (pin "6") (pinfunction "6_6") (pintype "bidirectional"))
    )
    (net (code "109") (name "unconnected-(RESET_BUTTON-Pad1)") (class "Default")
      (node (ref "RESET_BUTTON") (pin "1") (pinfunction "1_1") (pintype "passive"))
    )
    (net (code "110") (name "unconnected-(RESET_BUTTON-Pad2)") (class "Default")
      (node (ref "RESET_BUTTON") (pin "2") (pinfunction "2_2") (pintype "passive"))
    )
    (net (code "111") (name "unconnected-(RESET_BUTTON-Pad3)") (class "Default")
      (node (ref "RESET_BUTTON") (pin "3") (pinfunction "3_3") (pintype "passive"))
    )
    (net (code "112") (name "unconnected-(RESET_BUTTON-Pad4)") (class "Default")
      (node (ref "RESET_BUTTON") (pin "4") (pinfunction "4_4") (pintype "passive"))
    )
    (net (code "113") (name "unconnected-(RTC-32KHZ-Pad3)") (class "Default")
      (node (ref "RTC") (pin "3") (pinfunction "32KHZ_3") (pintype "bidirectional"))
    )
    (net (code "114") (name "unconnected-(RTC-CS-Pad1)") (class "Default")
      (node (ref "RTC") (pin "1") (pinfunction "CS_1") (pintype "bidirectional"))
    )
    (net (code "115") (name "unconnected-(RTC-DIN-Pad17)") (class "Default")
      (node (ref "RTC") (pin "17") (pinfunction "DIN_17") (pintype "bidirectional"))
    )
    (net (code "116") (name "unconnected-(RTC-DOUT-Pad19)") (class "Default")
      (node (ref "RTC") (pin "19") (pinfunction "DOUT_19") (pintype "bidirectional"))
    )
    (net (code "117") (name "unconnected-(RTC-GND-Pad2)") (class "Default")
      (node (ref "RTC") (pin "2") (pinfunction "GND_2") (pintype "bidirectional"))
    )
    (net (code "118") (name "unconnected-(RTC-GND-Pad7)") (class "Default")
      (node (ref "RTC") (pin "7") (pinfunction "GND_7") (pintype "bidirectional"))
    )
    (net (code "119") (name "unconnected-(RTC-GND-Pad8)") (class "Default")
      (node (ref "RTC") (pin "8") (pinfunction "GND_8") (pintype "bidirectional"))
    )
    (net (code "120") (name "unconnected-(RTC-GND-Pad9)") (class "Default")
      (node (ref "RTC") (pin "9") (pinfunction "GND_9") (pintype "bidirectional"))
    )
    (net (code "121") (name "unconnected-(RTC-GND-Pad10)") (class "Default")
      (node (ref "RTC") (pin "10") (pinfunction "GND_10") (pintype "bidirectional"))
    )
    (net (code "122") (name "unconnected-(RTC-GND-Pad11)") (class "Default")
      (node (ref "RTC") (pin "11") (pinfunction "GND_11") (pintype "bidirectional"))
    )
    (net (code "123") (name "unconnected-(RTC-GND-Pad12)") (class "Default")
      (node (ref "RTC") (pin "12") (pinfunction "GND_12") (pintype "bidirectional"))
    )
    (net (code "124") (name "unconnected-(RTC-GND-Pad13)") (class "Default")
      (node (ref "RTC") (pin "13") (pinfunction "GND_13") (pintype "bidirectional"))
    )
    (net (code "125") (name "unconnected-(RTC-GND-Pad14)") (class "Default")
      (node (ref "RTC") (pin "14") (pinfunction "GND_14") (pintype "bidirectional"))
    )
    (net (code "126") (name "unconnected-(RTC-GND-Pad15)") (class "Default")
      (node (ref "RTC") (pin "15") (pinfunction "GND_15") (pintype "bidirectional"))
    )
    (net (code "127") (name "unconnected-(RTC-INT{slash}SQW-Pad5)") (class "Default")
      (node (ref "RTC") (pin "5") (pinfunction "INT/SQW_5") (pintype "bidirectional"))
    )
    (net (code "128") (name "unconnected-(RTC-RST-Pad6)") (class "Default")
      (node (ref "RTC") (pin "6") (pinfunction "RST_6") (pintype "bidirectional"))
    )
    (net (code "129") (name "unconnected-(RTC-SCLK-Pad18)") (class "Default")
      (node (ref "RTC") (pin "18") (pinfunction "SCLK_18") (pintype "bidirectional"))
    )
    (net (code "130") (name "unconnected-(RTC-SCLK-Pad20)") (class "Default")
      (node (ref "RTC") (pin "20") (pinfunction "SCLK_20") (pintype "bidirectional"))
    )
    (net (code "131") (name "unconnected-(RTC-VBAT-Pad16)") (class "Default")
      (node (ref "RTC") (pin "16") (pinfunction "VBAT_16") (pintype "bidirectional"))
    )
    (net (code "132") (name "unconnected-(RTC-VCC-Pad4)") (class "Default")
      (node (ref "RTC") (pin "4") (pinfunction "VCC_4") (pintype "bidirectional"))
    )
  )
)
